# Dash_Switches_r2.net
KiCad netlist of a schematic drawn in EAGLE
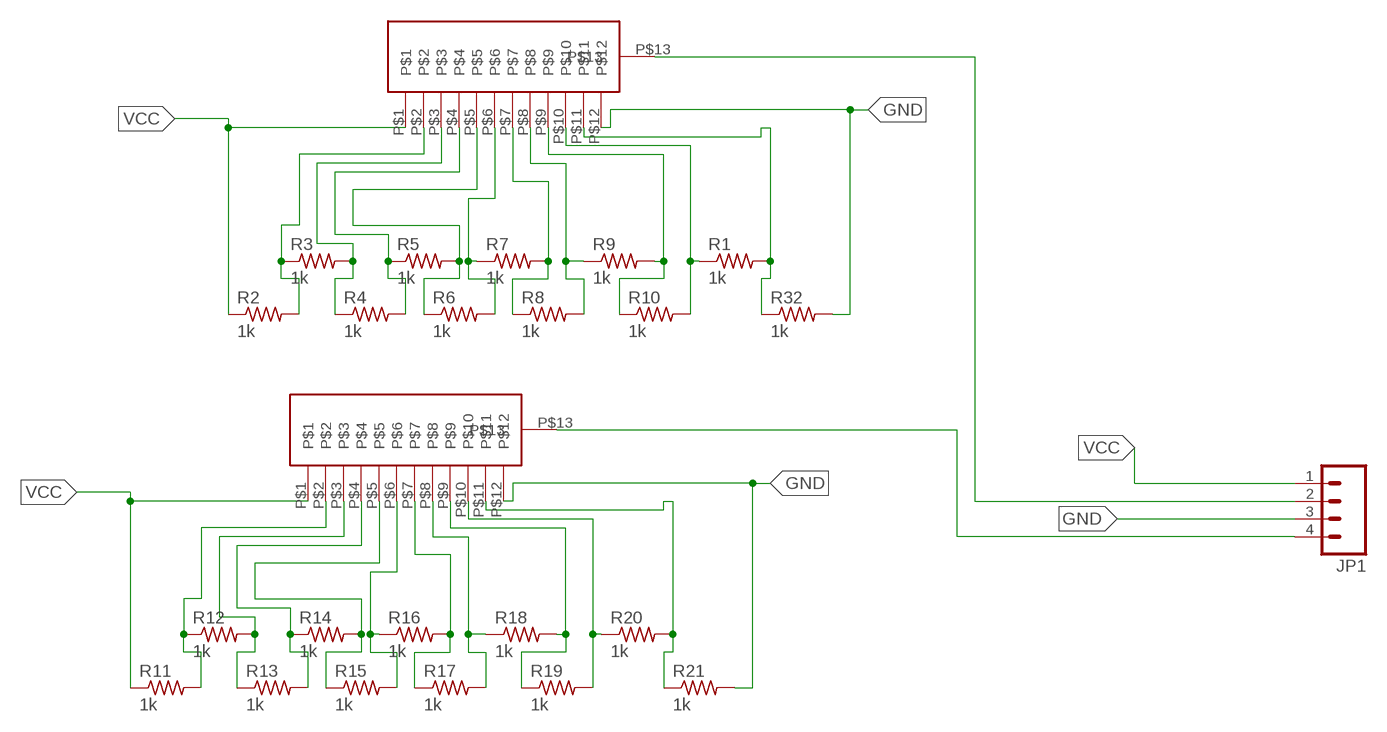
[diagram p0: schematic, sheet 1]

(export (version "E")
  (design (tool "Eeschema 10.0.6"))
  (components
    (comp (ref "JP1")
      (value "M04LOCK")
      (footprint "eagle-import:1X04_LOCK")
      (libsource (lib "eagle-import") (part "M04LOCK"))
    )
    (comp (ref "R1")
      (value "1k")
      (footprint "eagle-import:R0603")
      (libsource (lib "eagle-import") (part "R-US_R0603"))
    )
    (comp (ref "R2")
      (value "1k")
      (footprint "eagle-import:R0603")
      (libsource (lib "eagle-import") (part "R-US_R0603"))
    )
    (comp (ref "R3")
      (value "1k")
      (footprint "eagle-import:R0603")
      (libsource (lib "eagle-import") (part "R-US_R0603"))
    )
    (comp (ref "R4")
      (value "1k")
      (footprint "eagle-import:R0603")
      (libsource (lib "eagle-import") (part "R-US_R0603"))
    )
    (comp (ref "R5")
      (value "1k")
      (footprint "eagle-import:R0603")
      (libsource (lib "eagle-import") (part "R-US_R0603"))
    )
    (comp (ref "R6")
      (value "1k")
      (footprint "eagle-import:R0603")
      (libsource (lib "eagle-import") (part "R-US_R0603"))
    )
    (comp (ref "R7")
      (value "1k")
      (footprint "eagle-import:R0603")
      (libsource (lib "eagle-import") (part "R-US_R0603"))
    )
    (comp (ref "R8")
      (value "1k")
      (footprint "eagle-import:R0603")
      (libsource (lib "eagle-import") (part "R-US_R0603"))
    )
    (comp (ref "R9")
      (value "1k")
      (footprint "eagle-import:R0603")
      (libsource (lib "eagle-import") (part "R-US_R0603"))
    )
    (comp (ref "R10")
      (value "1k")
      (footprint "eagle-import:R0603")
      (libsource (lib "eagle-import") (part "R-US_R0603"))
    )
    (comp (ref "R11")
      (value "1k")
      (footprint "eagle-import:R0603")
      (libsource (lib "eagle-import") (part "R-US_R0603"))
    )
    (comp (ref "R12")
      (value "1k")
      (footprint "eagle-import:R0603")
      (libsource (lib "eagle-import") (part "R-US_R0603"))
    )
    (comp (ref "R13")
      (value "1k")
      (footprint "eagle-import:R0603")
      (libsource (lib "eagle-import") (part "R-US_R0603"))
    )
    (comp (ref "R14")
      (value "1k")
      (footprint "eagle-import:R0603")
      (libsource (lib "eagle-import") (part "R-US_R0603"))
    )
    (comp (ref "R15")
      (value "1k")
      (footprint "eagle-import:R0603")
      (libsource (lib "eagle-import") (part "R-US_R0603"))
    )
    (comp (ref "R16")
      (value "1k")
      (footprint "eagle-import:R0603")
      (libsource (lib "eagle-import") (part "R-US_R0603"))
    )
    (comp (ref "R17")
      (value "1k")
      (footprint "eagle-import:R0603")
      (libsource (lib "eagle-import") (part "R-US_R0603"))
    )
    (comp (ref "R18")
      (value "1k")
      (footprint "eagle-import:R0603")
      (libsource (lib "eagle-import") (part "R-US_R0603"))
    )
    (comp (ref "R19")
      (value "1k")
      (footprint "eagle-import:R0603")
      (libsource (lib "eagle-import") (part "R-US_R0603"))
    )
    (comp (ref "R20")
      (value "1k")
      (footprint "eagle-import:R0603")
      (libsource (lib "eagle-import") (part "R-US_R0603"))
    )
    (comp (ref "R21")
      (value "1k")
      (footprint "eagle-import:R0603")
      (libsource (lib "eagle-import") (part "R-US_R0603"))
    )
    (comp (ref "R32")
      (value "1k")
      (footprint "eagle-import:R0603")
      (libsource (lib "eagle-import") (part "R-US_R0603"))
    )
    (comp (ref "U$1")
      (value "ROTSWITCH")
      (footprint "eagle-import:ROTSWITCH")
      (libsource (lib "eagle-import") (part "ROTSWITCH"))
    )
    (comp (ref "U$2")
      (value "ROTSWITCH")
      (footprint "eagle-import:ROTSWITCH")
      (libsource (lib "eagle-import") (part "ROTSWITCH"))
    )
  )
  (nets
    (net (code "1") (name "GND") (class "Default")
      (node (ref "JP1") (pin "3") (pinfunction "3_3") (pintype "passive"))
      (node (ref "R21") (pin "2") (pinfunction "2_2") (pintype "passive"))
      (node (ref "R32") (pin "2") (pinfunction "2_2") (pintype "passive"))
      (node (ref "U$1") (pin "P$12") (pinfunction "P$12_P$12") (pintype "bidirectional"))
      (node (ref "U$2") (pin "P$12") (pinfunction "P$12_P$12") (pintype "bidirectional"))
    )
    (net (code "2") (name "Net-(JP1-Pad2)") (class "Default")
      (node (ref "JP1") (pin "2") (pinfunction "2_2") (pintype "passive"))
      (node (ref "U$1") (pin "P$13") (pinfunction "P$13_P$13") (pintype "bidirectional"))
    )
    (net (code "3") (name "Net-(JP1-Pad4)") (class "Default")
      (node (ref "JP1") (pin "4") (pinfunction "4_4") (pintype "passive"))
      (node (ref "U$2") (pin "P$13") (pinfunction "P$13_P$13") (pintype "bidirectional"))
    )
    (net (code "4") (name "Net-(R1-Pad1)") (class "Default")
      (node (ref "R1") (pin "1") (pinfunction "1_1") (pintype "passive"))
      (node (ref "R10") (pin "2") (pinfunction "2_2") (pintype "passive"))
      (node (ref "U$1") (pin "P$10") (pinfunction "P$10_P$10") (pintype "bidirectional"))
    )
    (net (code "5") (name "Net-(R1-Pad2)") (class "Default")
      (node (ref "R1") (pin "2") (pinfunction "2_2") (pintype "passive"))
      (node (ref "R32") (pin "1") (pinfunction "1_1") (pintype "passive"))
      (node (ref "U$1") (pin "P$11") (pinfunction "P$11_P$11") (pintype "bidirectional"))
    )
    (net (code "6") (name "Net-(R2-Pad2)") (class "Default")
      (node (ref "R2") (pin "2") (pinfunction "2_2") (pintype "passive"))
      (node (ref "R3") (pin "1") (pinfunction "1_1") (pintype "passive"))
      (node (ref "U$1") (pin "P$2") (pinfunction "P$2_P$2") (pintype "bidirectional"))
    )
    (net (code "7") (name "Net-(R3-Pad2)") (class "Default")
      (node (ref "R3") (pin "2") (pinfunction "2_2") (pintype "passive"))
      (node (ref "R4") (pin "1") (pinfunction "1_1") (pintype "passive"))
      (node (ref "U$1") (pin "P$3") (pinfunction "P$3_P$3") (pintype "bidirectional"))
    )
    (net (code "8") (name "Net-(R4-Pad2)") (class "Default")
      (node (ref "R4") (pin "2") (pinfunction "2_2") (pintype "passive"))
      (node (ref "R5") (pin "1") (pinfunction "1_1") (pintype "passive"))
      (node (ref "U$1") (pin "P$4") (pinfunction "P$4_P$4") (pintype "bidirectional"))
    )
    (net (code "9") (name "Net-(R5-Pad2)") (class "Default")
      (node (ref "R5") (pin "2") (pinfunction "2_2") (pintype "passive"))
      (node (ref "R6") (pin "1") (pinfunction "1_1") (pintype "passive"))
      (node (ref "U$1") (pin "P$5") (pinfunction "P$5_P$5") (pintype "bidirectional"))
    )
    (net (code "10") (name "Net-(R6-Pad2)") (class "Default")
      (node (ref "R6") (pin "2") (pinfunction "2_2") (pintype "passive"))
      (node (ref "R7") (pin "1") (pinfunction "1_1") (pintype "passive"))
      (node (ref "U$1") (pin "P$6") (pinfunction "P$6_P$6") (pintype "bidirectional"))
    )
    (net (code "11") (name "Net-(R7-Pad2)") (class "Default")
      (node (ref "R7") (pin "2") (pinfunction "2_2") (pintype "passive"))
      (node (ref "R8") (pin "1") (pinfunction "1_1") (pintype "passive"))
      (node (ref "U$1") (pin "P$7") (pinfunction "P$7_P$7") (pintype "bidirectional"))
    )
    (net (code "12") (name "Net-(R8-Pad2)") (class "Default")
      (node (ref "R8") (pin "2") (pinfunction "2_2") (pintype "passive"))
      (node (ref "R9") (pin "1") (pinfunction "1_1") (pintype "passive"))
      (node (ref "U$1") (pin "P$8") (pinfunction "P$8_P$8") (pintype "bidirectional"))
    )
    (net (code "13") (name "Net-(R10-Pad1)") (class "Default")
      (node (ref "R10") (pin "1") (pinfunction "1_1") (pintype "passive"))
      (node (ref "R9") (pin "2") (pinfunction "2_2") (pintype "passive"))
      (node (ref "U$1") (pin "P$9") (pinfunction "P$9_P$9") (pintype "bidirectional"))
    )
    (net (code "14") (name "Net-(R11-Pad2)") (class "Default")
      (node (ref "R11") (pin "2") (pinfunction "2_2") (pintype "passive"))
      (node (ref "R12") (pin "1") (pinfunction "1_1") (pintype "passive"))
      (node (ref "U$2") (pin "P$2") (pinfunction "P$2_P$2") (pintype "bidirectional"))
    )
    (net (code "15") (name "Net-(R12-Pad2)") (class "Default")
      (node (ref "R12") (pin "2") (pinfunction "2_2") (pintype "passive"))
      (node (ref "R13") (pin "1") (pinfunction "1_1") (pintype "passive"))
      (node (ref "U$2") (pin "P$3") (pinfunction "P$3_P$3") (pintype "bidirectional"))
    )
    (net (code "16") (name "Net-(R13-Pad2)") (class "Default")
      (node (ref "R13") (pin "2") (pinfunction "2_2") (pintype "passive"))
      (node (ref "R14") (pin "1") (pinfunction "1_1") (pintype "passive"))
      (node (ref "U$2") (pin "P$4") (pinfunction "P$4_P$4") (pintype "bidirectional"))
    )
    (net (code "17") (name "Net-(R14-Pad2)") (class "Default")
      (node (ref "R14") (pin "2") (pinfunction "2_2") (pintype "passive"))
      (node (ref "R15") (pin "1") (pinfunction "1_1") (pintype "passive"))
      (node (ref "U$2") (pin "P$5") (pinfunction "P$5_P$5") (pintype "bidirectional"))
    )
    (net (code "18") (name "Net-(R15-Pad2)") (class "Default")
      (node (ref "R15") (pin "2") (pinfunction "2_2") (pintype "passive"))
      (node (ref "R16") (pin "1") (pinfunction "1_1") (pintype "passive"))
      (node (ref "U$2") (pin "P$6") (pinfunction "P$6_P$6") (pintype "bidirectional"))
    )
    (net (code "19") (name "Net-(R16-Pad2)") (class "Default")
      (node (ref "R16") (pin "2") (pinfunction "2_2") (pintype "passive"))
      (node (ref "R17") (pin "1") (pinfunction "1_1") (pintype "passive"))
      (node (ref "U$2") (pin "P$7") (pinfunction "P$7_P$7") (pintype "bidirectional"))
    )
    (net (code "20") (name "Net-(R17-Pad2)") (class "Default")
      (node (ref "R17") (pin "2") (pinfunction "2_2") (pintype "passive"))
      (node (ref "R18") (pin "1") (pinfunction "1_1") (pintype "passive"))
      (node (ref "U$2") (pin "P$8") (pinfunction "P$8_P$8") (pintype "bidirectional"))
    )
    (net (code "21") (name "Net-(R18-Pad2)") (class "Default")
      (node (ref "R18") (pin "2") (pinfunction "2_2") (pintype "passive"))
      (node (ref "R19") (pin "1") (pinfunction "1_1") (pintype "passive"))
      (node (ref "U$2") (pin "P$9") (pinfunction "P$9_P$9") (pintype "bidirectional"))
    )
    (net (code "22") (name "Net-(R19-Pad2)") (class "Default")
      (node (ref "R19") (pin "2") (pinfunction "2_2") (pintype "passive"))
      (node (ref "R20") (pin "1") (pinfunction "1_1") (pintype "passive"))
      (node (ref "U$2") (pin "P$10") (pinfunction "P$10_P$10") (pintype "bidirectional"))
    )
    (net (code "23") (name "Net-(R20-Pad2)") (class "Default")
      (node (ref "R20") (pin "2") (pinfunction "2_2") (pintype "passive"))
      (node (ref "R21") (pin "1") (pinfunction "1_1") (pintype "passive"))
      (node (ref "U$2") (pin "P$11") (pinfunction "P$11_P$11") (pintype "bidirectional"))
    )
    (net (code "24") (name "VCC") (class "Default")
      (node (ref "JP1") (pin "1") (pinfunction "1_1") (pintype "passive"))
      (node (ref "R11") (pin "1") (pinfunction "1_1") (pintype "passive"))
      (node (ref "R2") (pin "1") (pinfunction "1_1") (pintype "passive"))
      (node (ref "U$1") (pin "P$1") (pinfunction "P$1_P$1") (pintype "bidirectional"))
      (node (ref "U$2") (pin "P$1") (pinfunction "P$1_P$1") (pintype "bidirectional"))
    )
  )
)
